# mirrored.net
KiCad netlist of a schematic drawn in EAGLE
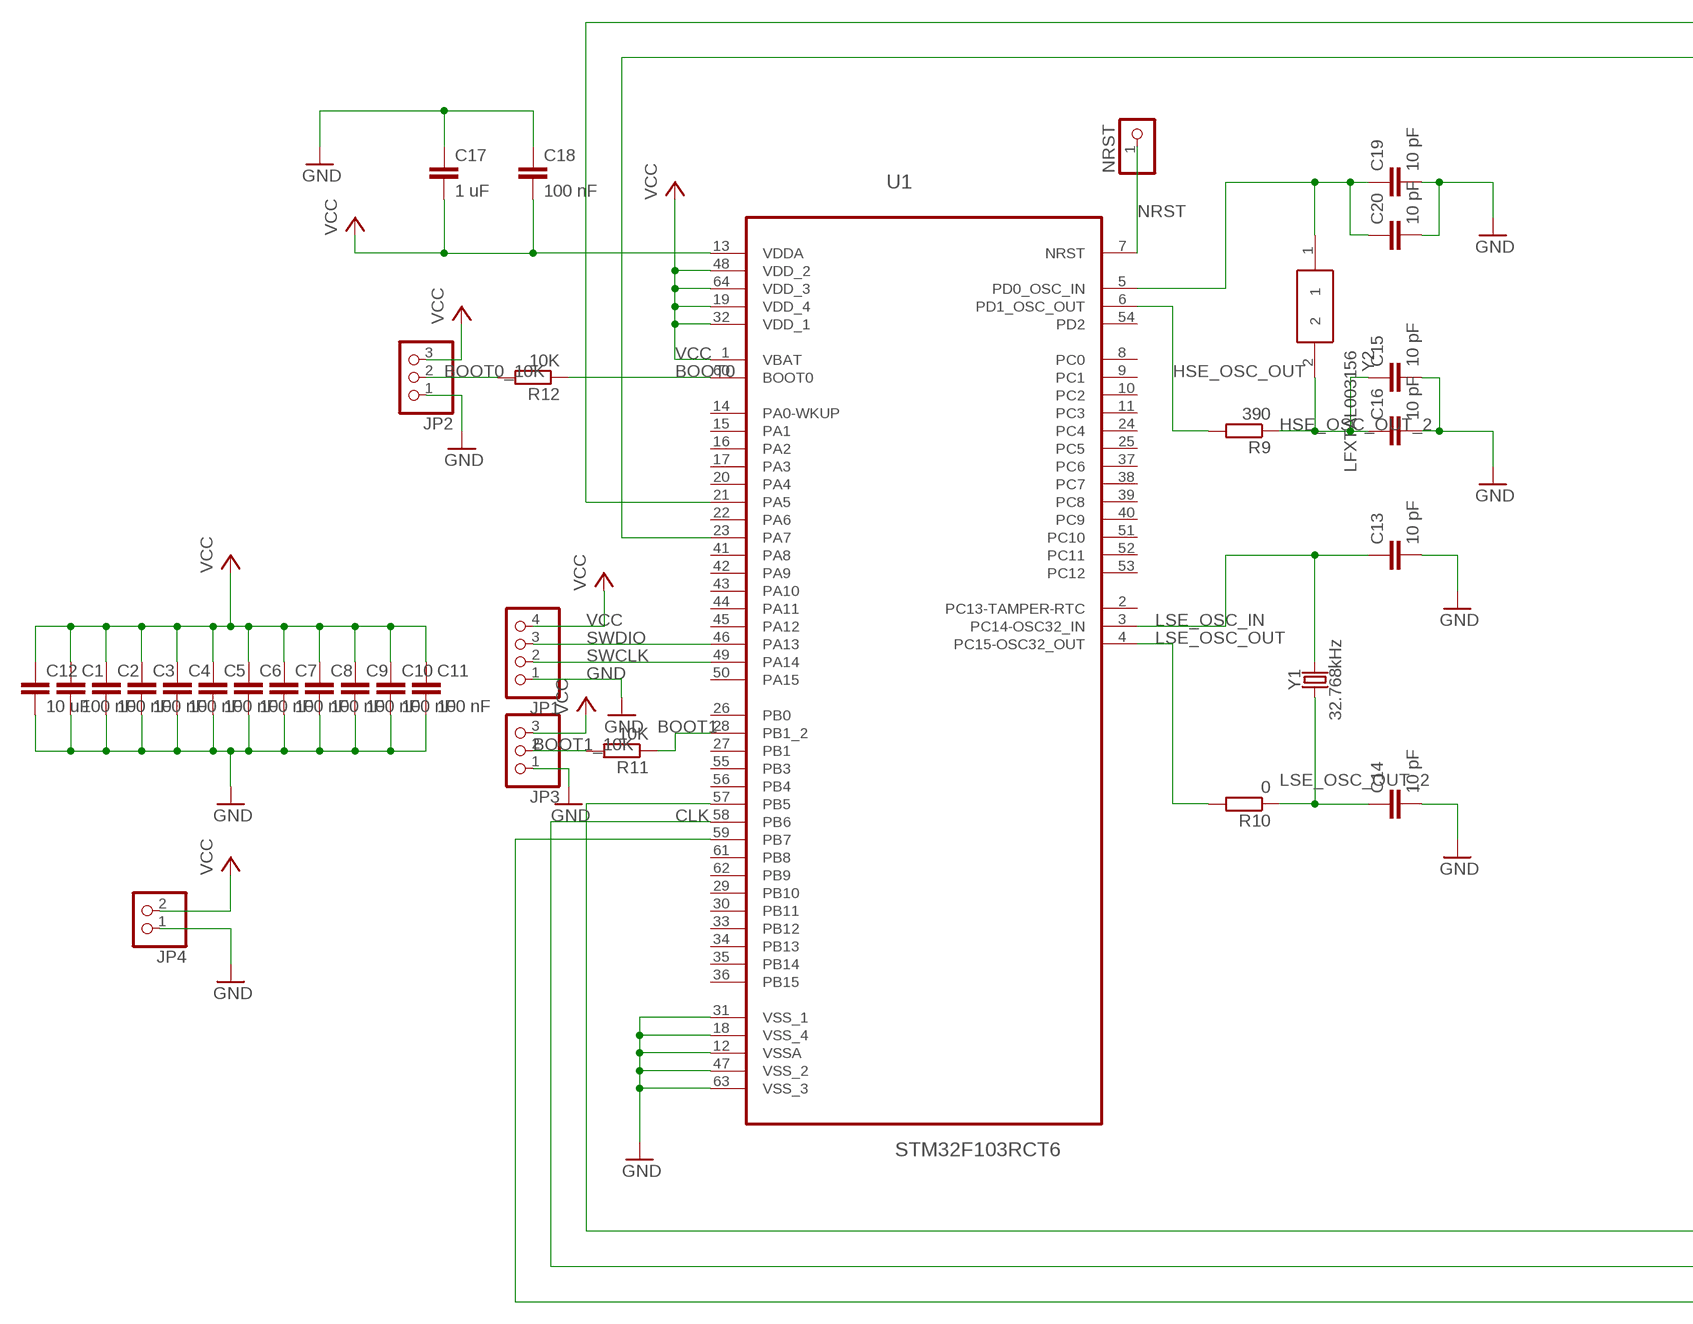
[diagram p0: schematic, sheet 1, part 1 of 2]
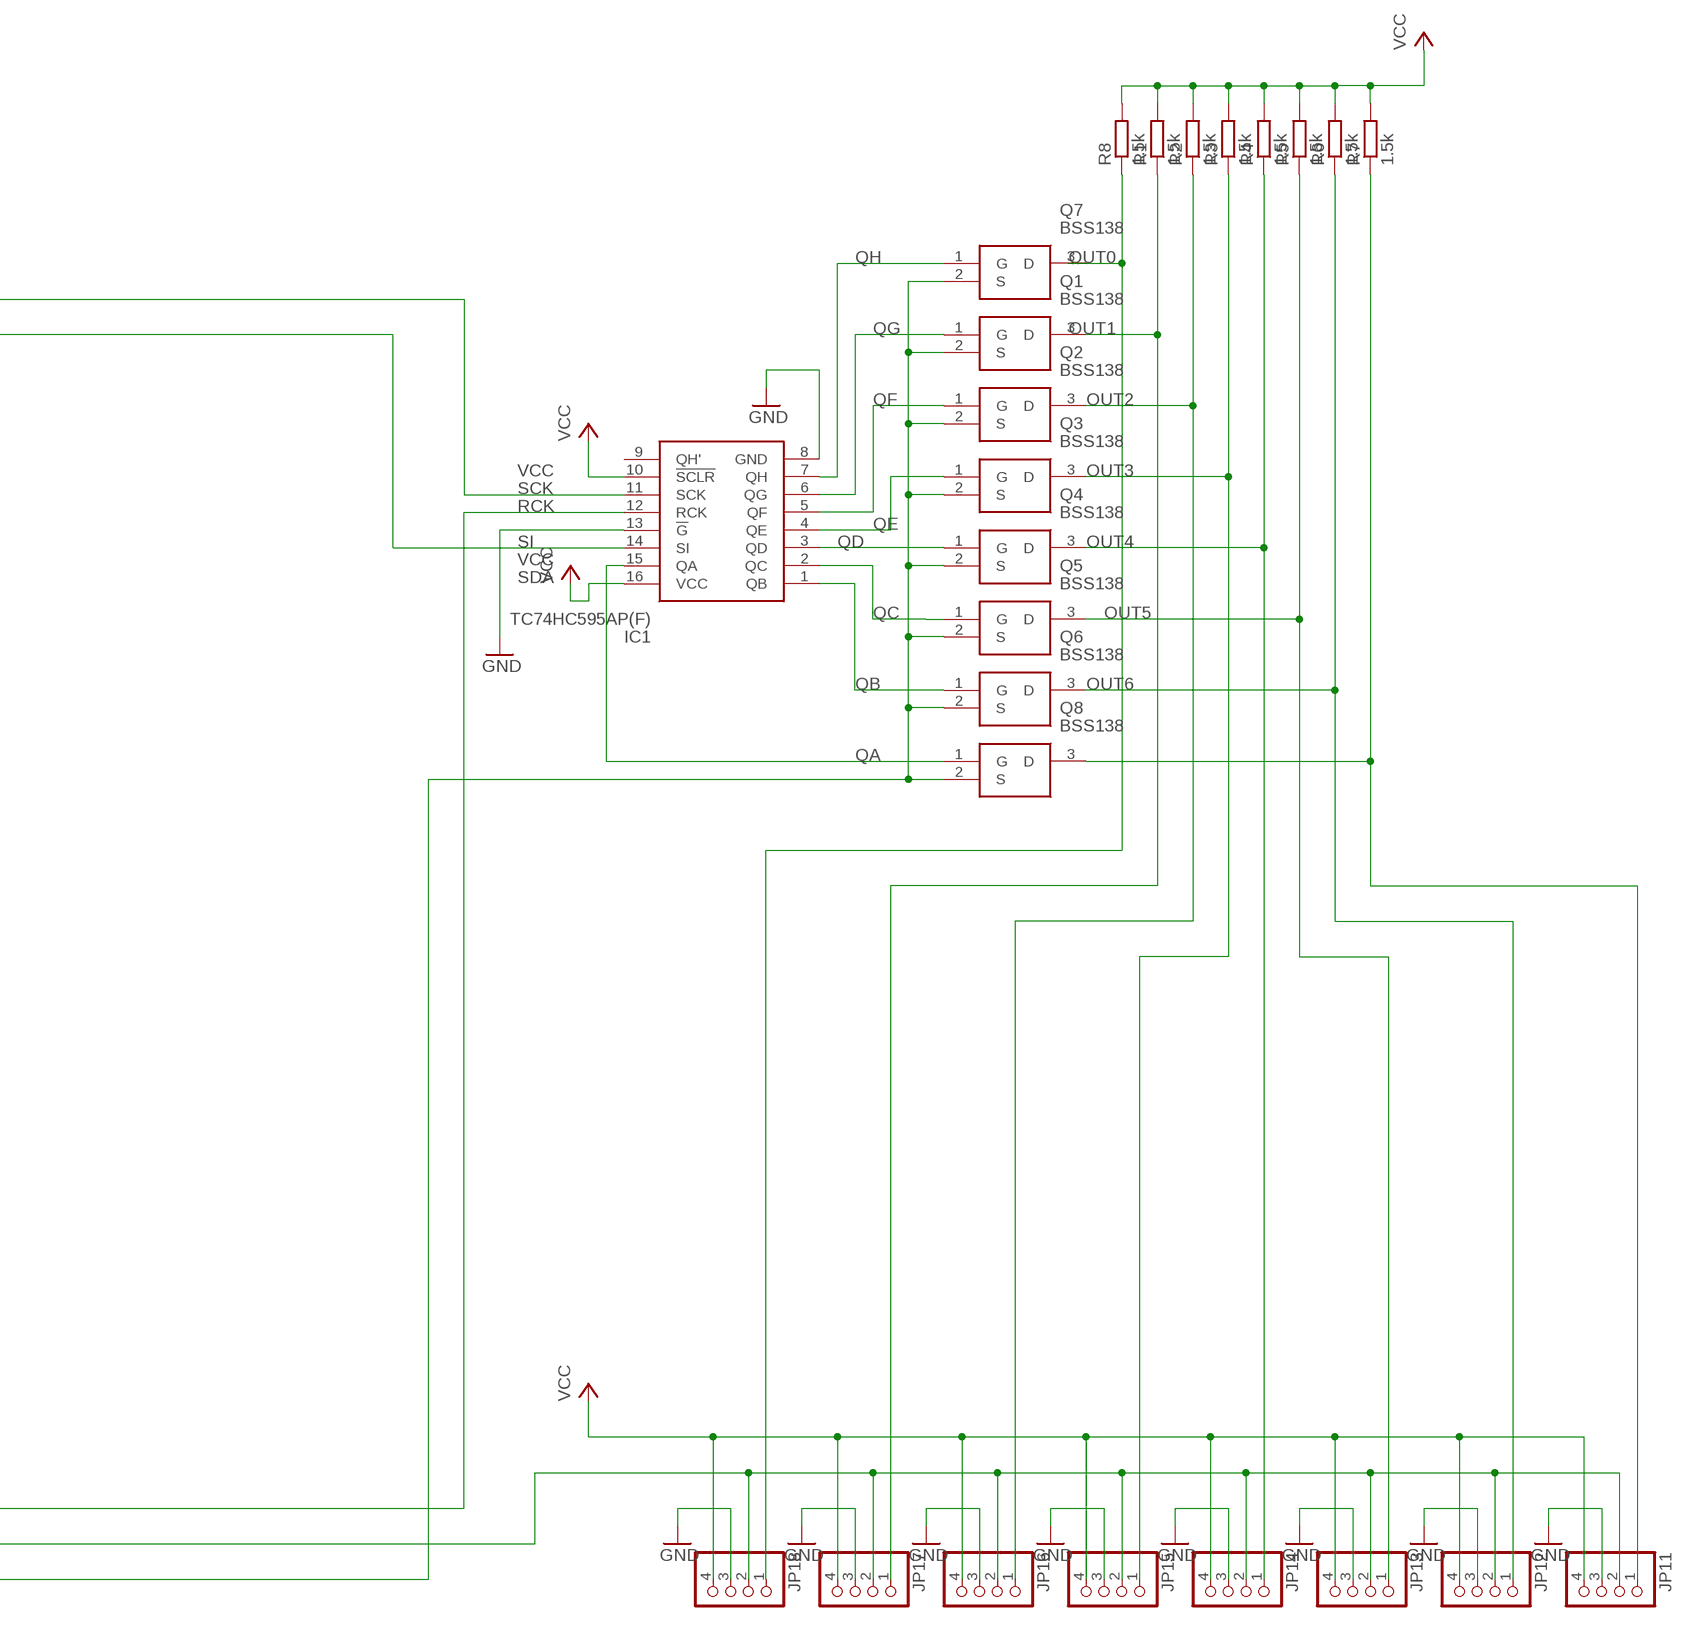
[diagram p1: schematic, sheet 1, part 2 of 2]

(export (version "E")
  (design (tool "Eeschema 10.0.6"))
  (components
    (comp (ref "C1")
      (value "100 nF")
      (footprint "eagle-import:C0603")
      (libsource (lib "eagle-import") (part "C-EUC0603"))
    )
    (comp (ref "C2")
      (value "100 nF")
      (footprint "eagle-import:C0603")
      (libsource (lib "eagle-import") (part "C-EUC0603"))
    )
    (comp (ref "C3")
      (value "100 nF")
      (footprint "eagle-import:C0603")
      (libsource (lib "eagle-import") (part "C-EUC0603"))
    )
    (comp (ref "C4")
      (value "100 nF")
      (footprint "eagle-import:C0603")
      (libsource (lib "eagle-import") (part "C-EUC0603"))
    )
    (comp (ref "C5")
      (value "100 nF")
      (footprint "eagle-import:C0603")
      (libsource (lib "eagle-import") (part "C-EUC0603"))
    )
    (comp (ref "C6")
      (value "100 nF")
      (footprint "eagle-import:C0603")
      (libsource (lib "eagle-import") (part "C-EUC0603"))
    )
    (comp (ref "C7")
      (value "100 nF")
      (footprint "eagle-import:C0603")
      (libsource (lib "eagle-import") (part "C-EUC0603"))
    )
    (comp (ref "C8")
      (value "100 nF")
      (footprint "eagle-import:C0603")
      (libsource (lib "eagle-import") (part "C-EUC0603"))
    )
    (comp (ref "C9")
      (value "100 nF")
      (footprint "eagle-import:C0603")
      (libsource (lib "eagle-import") (part "C-EUC0603"))
    )
    (comp (ref "C10")
      (value "100 nF")
      (footprint "eagle-import:C0603")
      (libsource (lib "eagle-import") (part "C-EUC0603"))
    )
    (comp (ref "C11")
      (value "100 nF")
      (footprint "eagle-import:C0603")
      (libsource (lib "eagle-import") (part "C-EUC0603"))
    )
    (comp (ref "C12")
      (value "10 uF")
      (footprint "eagle-import:C0603")
      (libsource (lib "eagle-import") (part "resistor_348_C-EUC0603"))
    )
    (comp (ref "C13")
      (value "10 pF")
      (footprint "eagle-import:C0805")
      (libsource (lib "eagle-import") (part "resistor_348_C-EUC0805"))
    )
    (comp (ref "C14")
      (value "10 pF")
      (footprint "eagle-import:C0805")
      (libsource (lib "eagle-import") (part "resistor_348_C-EUC0805"))
    )
    (comp (ref "C15")
      (value "10 pF")
      (footprint "eagle-import:C0805")
      (libsource (lib "eagle-import") (part "resistor_348_C-EUC0805"))
    )
    (comp (ref "C16")
      (value "10 pF")
      (footprint "eagle-import:C0805")
      (libsource (lib "eagle-import") (part "resistor_348_C-EUC0805"))
    )
    (comp (ref "C17")
      (value "1 uF")
      (footprint "eagle-import:C0603")
      (libsource (lib "eagle-import") (part "C-EUC0603"))
    )
    (comp (ref "C18")
      (value "100 nF")
      (footprint "eagle-import:C0603")
      (libsource (lib "eagle-import") (part "C-EUC0603"))
    )
    (comp (ref "C19")
      (value "10 pF")
      (footprint "eagle-import:C0805")
      (libsource (lib "eagle-import") (part "resistor_348_C-EUC0805"))
    )
    (comp (ref "C20")
      (value "10 pF")
      (footprint "eagle-import:C0805")
      (libsource (lib "eagle-import") (part "resistor_348_C-EUC0805"))
    )
    (comp (ref "IC1")
      (value "TC74HC595AP(F)")
      (footprint "eagle-import:DIP762W60P254L1925H445Q16N")
      (fields (field (name "RS_PART_NUMBER") "5400095P"))
      (libsource (lib "eagle-import") (part "TC74HC595AP(F)"))
    )
    (comp (ref "JP1")
      (value "PINHD-1X4")
      (footprint "eagle-import:1X04")
      (libsource (lib "eagle-import") (part "PINHD-1X4"))
    )
    (comp (ref "JP2")
      (value "PINHD-1X3")
      (footprint "eagle-import:1X03")
      (libsource (lib "eagle-import") (part "PINHD-1X3"))
    )
    (comp (ref "JP3")
      (value "PINHD-1X3")
      (footprint "eagle-import:1X03")
      (libsource (lib "eagle-import") (part "PINHD-1X3"))
    )
    (comp (ref "JP4")
      (value "PINHD-1X2")
      (footprint "eagle-import:1X02")
      (libsource (lib "eagle-import") (part "PINHD-1X2"))
    )
    (comp (ref "JP11")
      (value "PINHD-1X4")
      (footprint "eagle-import:1X04")
      (libsource (lib "eagle-import") (part "PINHD-1X4"))
    )
    (comp (ref "JP12")
      (value "PINHD-1X4")
      (footprint "eagle-import:1X04")
      (libsource (lib "eagle-import") (part "PINHD-1X4"))
    )
    (comp (ref "JP13")
      (value "PINHD-1X4")
      (footprint "eagle-import:1X04")
      (libsource (lib "eagle-import") (part "PINHD-1X4"))
    )
    (comp (ref "JP14")
      (value "PINHD-1X4")
      (footprint "eagle-import:1X04")
      (libsource (lib "eagle-import") (part "PINHD-1X4"))
    )
    (comp (ref "JP15")
      (value "PINHD-1X4")
      (footprint "eagle-import:1X04")
      (libsource (lib "eagle-import") (part "PINHD-1X4"))
    )
    (comp (ref "JP16")
      (value "PINHD-1X4")
      (footprint "eagle-import:1X04")
      (libsource (lib "eagle-import") (part "PINHD-1X4"))
    )
    (comp (ref "JP17")
      (value "PINHD-1X4")
      (footprint "eagle-import:1X04")
      (libsource (lib "eagle-import") (part "PINHD-1X4"))
    )
    (comp (ref "JP18")
      (value "PINHD-1X4")
      (footprint "eagle-import:1X04")
      (libsource (lib "eagle-import") (part "PINHD-1X4"))
    )
    (comp (ref "NRST")
      (value "PINHD-1X1")
      (footprint "eagle-import:1X01")
      (libsource (lib "eagle-import") (part "PINHD-1X1"))
    )
    (comp (ref "Q1")
      (value "BSS138")
      (footprint "eagle-import:SOT95P240X120-3N")
      (fields (field (name "MOUSER_PART_NUMBER") "512-BSS138") (field (name "RS_PART_NUMBER") "1241694"))
      (libsource (lib "eagle-import") (part "BSS138"))
    )
    (comp (ref "Q2")
      (value "BSS138")
      (footprint "eagle-import:SOT95P240X120-3N")
      (fields (field (name "MOUSER_PART_NUMBER") "512-BSS138") (field (name "RS_PART_NUMBER") "1241694"))
      (libsource (lib "eagle-import") (part "BSS138"))
    )
    (comp (ref "Q3")
      (value "BSS138")
      (footprint "eagle-import:SOT95P240X120-3N")
      (fields (field (name "MOUSER_PART_NUMBER") "512-BSS138") (field (name "RS_PART_NUMBER") "1241694"))
      (libsource (lib "eagle-import") (part "BSS138"))
    )
    (comp (ref "Q4")
      (value "BSS138")
      (footprint "eagle-import:SOT95P240X120-3N")
      (fields (field (name "MOUSER_PART_NUMBER") "512-BSS138") (field (name "RS_PART_NUMBER") "1241694"))
      (libsource (lib "eagle-import") (part "BSS138"))
    )
    (comp (ref "Q5")
      (value "BSS138")
      (footprint "eagle-import:SOT95P240X120-3N")
      (fields (field (name "MOUSER_PART_NUMBER") "512-BSS138") (field (name "RS_PART_NUMBER") "1241694"))
      (libsource (lib "eagle-import") (part "BSS138"))
    )
    (comp (ref "Q6")
      (value "BSS138")
      (footprint "eagle-import:SOT95P240X120-3N")
      (fields (field (name "MOUSER_PART_NUMBER") "512-BSS138") (field (name "RS_PART_NUMBER") "1241694"))
      (libsource (lib "eagle-import") (part "BSS138"))
    )
    (comp (ref "Q7")
      (value "BSS138")
      (footprint "eagle-import:SOT95P240X120-3N")
      (fields (field (name "MOUSER_PART_NUMBER") "512-BSS138") (field (name "RS_PART_NUMBER") "1241694"))
      (libsource (lib "eagle-import") (part "BSS138"))
    )
    (comp (ref "Q8")
      (value "BSS138")
      (footprint "eagle-import:SOT95P240X120-3N")
      (fields (field (name "MOUSER_PART_NUMBER") "512-BSS138") (field (name "RS_PART_NUMBER") "1241694"))
      (libsource (lib "eagle-import") (part "BSS138"))
    )
    (comp (ref "R1")
      (value "1.5k")
      (footprint "eagle-import:0207_15")
      (libsource (lib "eagle-import") (part "R-EU_0207/15"))
    )
    (comp (ref "R2")
      (value "1.5k")
      (footprint "eagle-import:0207_15")
      (libsource (lib "eagle-import") (part "R-EU_0207/15"))
    )
    (comp (ref "R3")
      (value "1.5k")
      (footprint "eagle-import:0207_15")
      (libsource (lib "eagle-import") (part "R-EU_0207/15"))
    )
    (comp (ref "R4")
      (value "1.5k")
      (footprint "eagle-import:0207_15")
      (libsource (lib "eagle-import") (part "R-EU_0207/15"))
    )
    (comp (ref "R5")
      (value "1.5k")
      (footprint "eagle-import:0207_15")
      (libsource (lib "eagle-import") (part "R-EU_0207/15"))
    )
    (comp (ref "R6")
      (value "1.5k")
      (footprint "eagle-import:0207_15")
      (libsource (lib "eagle-import") (part "R-EU_0207/15"))
    )
    (comp (ref "R7")
      (value "1.5k")
      (footprint "eagle-import:0207_15")
      (libsource (lib "eagle-import") (part "R-EU_0207/15"))
    )
    (comp (ref "R8")
      (value "1.5k")
      (footprint "eagle-import:0207_15")
      (libsource (lib "eagle-import") (part "R-EU_0207/15"))
    )
    (comp (ref "R9")
      (value "390")
      (footprint "eagle-import:0207_15")
      (libsource (lib "eagle-import") (part "R-EU_0207/15"))
    )
    (comp (ref "R10")
      (value "0")
      (footprint "eagle-import:0207_15")
      (libsource (lib "eagle-import") (part "R-EU_0207/15"))
    )
    (comp (ref "R11")
      (value "10K")
      (footprint "eagle-import:0207_15")
      (libsource (lib "eagle-import") (part "R-EU_0207/15"))
    )
    (comp (ref "R12")
      (value "10K")
      (footprint "eagle-import:0207_15")
      (libsource (lib "eagle-import") (part "R-EU_0207/15"))
    )
    (comp (ref "U1")
      (value "STM32F103RCT6")
      (footprint "eagle-import:QFP50P1200X1200X160-64N")
      (fields (field (name "MF") "STMicroelectronics"))
      (libsource (lib "eagle-import") (part "STM32F103RCT6"))
    )
    (comp (ref "Y1")
      (value "32.768kHz")
      (footprint "eagle-import:CRYSTAL-PTH-2X6-CYL")
      (libsource (lib "eagle-import") (part "CRYSTAL-32.768KHZPTH-2X6"))
    )
    (comp (ref "Y2")
      (value "LFXTAL003156")
      (footprint "eagle-import:IQD-HC-49-4H")
      (fields (field (name "RS_PART_NUMBER") "1533666"))
      (libsource (lib "eagle-import") (part "LFXTAL003156"))
    )
  )
  (nets
    (net (code "1") (name "/BOOT0") (class "Default")
      (node (ref "R12") (pin "1") (pinfunction "1_1") (pintype "passive"))
      (node (ref "U1") (pin "60") (pinfunction "BOOT0_60") (pintype "passive"))
    )
    (net (code "2") (name "/BOOT0_10K") (class "Default")
      (node (ref "JP2") (pin "2") (pinfunction "2_2") (pintype "passive"))
      (node (ref "R12") (pin "2") (pinfunction "2_2") (pintype "passive"))
    )
    (net (code "3") (name "/BOOT1") (class "Default")
      (node (ref "R11") (pin "1") (pinfunction "1_1") (pintype "passive"))
      (node (ref "U1") (pin "28") (pinfunction "PB1_2_28") (pintype "bidirectional"))
    )
    (net (code "4") (name "/BOOT1_10K") (class "Default")
      (node (ref "JP3") (pin "2") (pinfunction "2_2") (pintype "passive"))
      (node (ref "R11") (pin "2") (pinfunction "2_2") (pintype "passive"))
    )
    (net (code "5") (name "/CLK") (class "Default")
      (node (ref "JP11") (pin "2") (pinfunction "2_2") (pintype "passive"))
      (node (ref "JP12") (pin "2") (pinfunction "2_2") (pintype "passive"))
      (node (ref "JP13") (pin "2") (pinfunction "2_2") (pintype "passive"))
      (node (ref "JP14") (pin "2") (pinfunction "2_2") (pintype "passive"))
      (node (ref "JP15") (pin "2") (pinfunction "2_2") (pintype "passive"))
      (node (ref "JP16") (pin "2") (pinfunction "2_2") (pintype "passive"))
      (node (ref "JP17") (pin "2") (pinfunction "2_2") (pintype "passive"))
      (node (ref "JP18") (pin "2") (pinfunction "2_2") (pintype "passive"))
      (node (ref "U1") (pin "58") (pinfunction "PB6_58") (pintype "bidirectional"))
    )
    (net (code "6") (name "/HSE_OSC_OUT") (class "Default")
      (node (ref "R9") (pin "2") (pinfunction "2_2") (pintype "passive"))
      (node (ref "U1") (pin "6") (pinfunction "PD1_OSC_OUT_6") (pintype "output"))
    )
    (net (code "7") (name "/HSE_OSC_OUT_2") (class "Default")
      (node (ref "C15") (pin "1") (pinfunction "1_1") (pintype "passive"))
      (node (ref "C16") (pin "1") (pinfunction "1_1") (pintype "passive"))
      (node (ref "R9") (pin "1") (pinfunction "1_1") (pintype "passive"))
      (node (ref "Y2") (pin "2") (pinfunction "2_2") (pintype "bidirectional"))
    )
    (net (code "8") (name "/LSE_OSC_IN") (class "Default")
      (node (ref "C13") (pin "1") (pinfunction "1_1") (pintype "passive"))
      (node (ref "U1") (pin "3") (pinfunction "PC14-OSC32_IN_3") (pintype "input"))
      (node (ref "Y1") (pin "2") (pinfunction "2_2") (pintype "passive"))
    )
    (net (code "9") (name "/LSE_OSC_OUT") (class "Default")
      (node (ref "R10") (pin "2") (pinfunction "2_2") (pintype "passive"))
      (node (ref "U1") (pin "4") (pinfunction "PC15-OSC32_OUT_4") (pintype "output"))
    )
    (net (code "10") (name "/LSE_OSC_OUT_2") (class "Default")
      (node (ref "C14") (pin "1") (pinfunction "1_1") (pintype "passive"))
      (node (ref "R10") (pin "1") (pinfunction "1_1") (pintype "passive"))
      (node (ref "Y1") (pin "1") (pinfunction "1_1") (pintype "passive"))
    )
    (net (code "11") (name "/NRST") (class "Default")
      (node (ref "NRST") (pin "1") (pinfunction "1_1") (pintype "passive"))
      (node (ref "U1") (pin "7") (pinfunction "NRST_7") (pintype "output"))
    )
    (net (code "12") (name "/OUT0") (class "Default")
      (node (ref "JP18") (pin "1") (pinfunction "1_1") (pintype "passive"))
      (node (ref "Q7") (pin "3") (pinfunction "D_3") (pintype "bidirectional"))
      (node (ref "R8") (pin "1") (pinfunction "1_1") (pintype "passive"))
    )
    (net (code "13") (name "/OUT1") (class "Default")
      (node (ref "JP17") (pin "1") (pinfunction "1_1") (pintype "passive"))
      (node (ref "Q1") (pin "3") (pinfunction "D_3") (pintype "bidirectional"))
      (node (ref "R1") (pin "1") (pinfunction "1_1") (pintype "passive"))
    )
    (net (code "14") (name "/OUT2") (class "Default")
      (node (ref "JP16") (pin "1") (pinfunction "1_1") (pintype "passive"))
      (node (ref "Q2") (pin "3") (pinfunction "D_3") (pintype "bidirectional"))
      (node (ref "R2") (pin "1") (pinfunction "1_1") (pintype "passive"))
    )
    (net (code "15") (name "/OUT3") (class "Default")
      (node (ref "JP15") (pin "1") (pinfunction "1_1") (pintype "passive"))
      (node (ref "Q3") (pin "3") (pinfunction "D_3") (pintype "bidirectional"))
      (node (ref "R3") (pin "1") (pinfunction "1_1") (pintype "passive"))
    )
    (net (code "16") (name "/OUT4") (class "Default")
      (node (ref "JP14") (pin "1") (pinfunction "1_1") (pintype "passive"))
      (node (ref "Q4") (pin "3") (pinfunction "D_3") (pintype "bidirectional"))
      (node (ref "R4") (pin "1") (pinfunction "1_1") (pintype "passive"))
    )
    (net (code "17") (name "/OUT5") (class "Default")
      (node (ref "JP13") (pin "1") (pinfunction "1_1") (pintype "passive"))
      (node (ref "Q5") (pin "3") (pinfunction "D_3") (pintype "bidirectional"))
      (node (ref "R5") (pin "1") (pinfunction "1_1") (pintype "passive"))
    )
    (net (code "18") (name "/OUT6") (class "Default")
      (node (ref "JP12") (pin "1") (pinfunction "1_1") (pintype "passive"))
      (node (ref "Q6") (pin "3") (pinfunction "D_3") (pintype "bidirectional"))
      (node (ref "R6") (pin "1") (pinfunction "1_1") (pintype "passive"))
    )
    (net (code "19") (name "/QA") (class "Default")
      (node (ref "IC1") (pin "15") (pinfunction "QA_15") (pintype "bidirectional"))
      (node (ref "Q8") (pin "1") (pinfunction "G_1") (pintype "bidirectional"))
    )
    (net (code "20") (name "/QB") (class "Default")
      (node (ref "IC1") (pin "1") (pinfunction "QB_1") (pintype "bidirectional"))
      (node (ref "Q6") (pin "1") (pinfunction "G_1") (pintype "bidirectional"))
    )
    (net (code "21") (name "/QC") (class "Default")
      (node (ref "IC1") (pin "2") (pinfunction "QC_2") (pintype "bidirectional"))
      (node (ref "Q5") (pin "1") (pinfunction "G_1") (pintype "bidirectional"))
    )
    (net (code "22") (name "/QD") (class "Default")
      (node (ref "IC1") (pin "3") (pinfunction "QD_3") (pintype "bidirectional"))
      (node (ref "Q4") (pin "1") (pinfunction "G_1") (pintype "bidirectional"))
    )
    (net (code "23") (name "/QE") (class "Default")
      (node (ref "IC1") (pin "4") (pinfunction "QE_4") (pintype "bidirectional"))
      (node (ref "Q3") (pin "1") (pinfunction "G_1") (pintype "bidirectional"))
    )
    (net (code "24") (name "/QF") (class "Default")
      (node (ref "IC1") (pin "5") (pinfunction "QF_5") (pintype "bidirectional"))
      (node (ref "Q2") (pin "1") (pinfunction "G_1") (pintype "bidirectional"))
    )
    (net (code "25") (name "/QG") (class "Default")
      (node (ref "IC1") (pin "6") (pinfunction "QG_6") (pintype "bidirectional"))
      (node (ref "Q1") (pin "1") (pinfunction "G_1") (pintype "bidirectional"))
    )
    (net (code "26") (name "/QH") (class "Default")
      (node (ref "IC1") (pin "7") (pinfunction "QH_7") (pintype "bidirectional"))
      (node (ref "Q7") (pin "1") (pinfunction "G_1") (pintype "bidirectional"))
    )
    (net (code "27") (name "/RCK") (class "Default")
      (node (ref "IC1") (pin "12") (pinfunction "RCK_12") (pintype "bidirectional"))
      (node (ref "U1") (pin "57") (pinfunction "PB5_57") (pintype "bidirectional"))
    )
    (net (code "28") (name "/SCK") (class "Default")
      (node (ref "IC1") (pin "11") (pinfunction "SCK_11") (pintype "bidirectional"))
      (node (ref "U1") (pin "21") (pinfunction "PA5_21") (pintype "bidirectional"))
    )
    (net (code "29") (name "/SDA") (class "Default")
      (node (ref "Q1") (pin "2") (pinfunction "S_2") (pintype "bidirectional"))
      (node (ref "Q2") (pin "2") (pinfunction "S_2") (pintype "bidirectional"))
      (node (ref "Q3") (pin "2") (pinfunction "S_2") (pintype "bidirectional"))
      (node (ref "Q4") (pin "2") (pinfunction "S_2") (pintype "bidirectional"))
      (node (ref "Q5") (pin "2") (pinfunction "S_2") (pintype "bidirectional"))
      (node (ref "Q6") (pin "2") (pinfunction "S_2") (pintype "bidirectional"))
      (node (ref "Q7") (pin "2") (pinfunction "S_2") (pintype "bidirectional"))
      (node (ref "Q8") (pin "2") (pinfunction "S_2") (pintype "bidirectional"))
      (node (ref "U1") (pin "59") (pinfunction "PB7_59") (pintype "power_in"))
    )
    (net (code "30") (name "/SI") (class "Default")
      (node (ref "IC1") (pin "14") (pinfunction "SI_14") (pintype "bidirectional"))
      (node (ref "U1") (pin "23") (pinfunction "PA7_23") (pintype "power_in"))
    )
    (net (code "31") (name "/SWCLK") (class "Default")
      (node (ref "JP1") (pin "2") (pinfunction "2_2") (pintype "passive"))
      (node (ref "U1") (pin "49") (pinfunction "PA14_49") (pintype "bidirectional"))
    )
    (net (code "32") (name "/SWDIO") (class "Default")
      (node (ref "JP1") (pin "3") (pinfunction "3_3") (pintype "passive"))
      (node (ref "U1") (pin "46") (pinfunction "PA13_46") (pintype "bidirectional"))
    )
    (net (code "33") (name "GND") (class "Default")
      (node (ref "C1") (pin "2") (pinfunction "2_2") (pintype "passive"))
      (node (ref "C10") (pin "2") (pinfunction "2_2") (pintype "passive"))
      (node (ref "C11") (pin "2") (pinfunction "2_2") (pintype "passive"))
      (node (ref "C12") (pin "2") (pinfunction "2_2") (pintype "passive"))
      (node (ref "C13") (pin "2") (pinfunction "2_2") (pintype "passive"))
      (node (ref "C14") (pin "2") (pinfunction "2_2") (pintype "passive"))
      (node (ref "C15") (pin "2") (pinfunction "2_2") (pintype "passive"))
      (node (ref "C16") (pin "2") (pinfunction "2_2") (pintype "passive"))
      (node (ref "C17") (pin "1") (pinfunction "1_1") (pintype "passive"))
      (node (ref "C18") (pin "1") (pinfunction "1_1") (pintype "passive"))
      (node (ref "C19") (pin "2") (pinfunction "2_2") (pintype "passive"))
      (node (ref "C2") (pin "2") (pinfunction "2_2") (pintype "passive"))
      (node (ref "C20") (pin "2") (pinfunction "2_2") (pintype "passive"))
      (node (ref "C3") (pin "2") (pinfunction "2_2") (pintype "passive"))
      (node (ref "C4") (pin "2") (pinfunction "2_2") (pintype "passive"))
      (node (ref "C5") (pin "2") (pinfunction "2_2") (pintype "passive"))
      (node (ref "C6") (pin "2") (pinfunction "2_2") (pintype "passive"))
      (node (ref "C7") (pin "2") (pinfunction "2_2") (pintype "passive"))
      (node (ref "C8") (pin "2") (pinfunction "2_2") (pintype "passive"))
      (node (ref "C9") (pin "2") (pinfunction "2_2") (pintype "passive"))
      (node (ref "IC1") (pin "13") (pinfunction "~{G}_13") (pintype "bidirectional"))
      (node (ref "IC1") (pin "8") (pinfunction "GND_8") (pintype "bidirectional"))
      (node (ref "JP1") (pin "1") (pinfunction "1_1") (pintype "passive"))
      (node (ref "JP11") (pin "3") (pinfunction "3_3") (pintype "passive"))
      (node (ref "JP12") (pin "3") (pinfunction "3_3") (pintype "passive"))
      (node (ref "JP13") (pin "3") (pinfunction "3_3") (pintype "passive"))
      (node (ref "JP14") (pin "3") (pinfunction "3_3") (pintype "passive"))
      (node (ref "JP15") (pin "3") (pinfunction "3_3") (pintype "passive"))
      (node (ref "JP16") (pin "3") (pinfunction "3_3") (pintype "passive"))
      (node (ref "JP17") (pin "3") (pinfunction "3_3") (pintype "passive"))
      (node (ref "JP18") (pin "3") (pinfunction "3_3") (pintype "passive"))
      (node (ref "JP2") (pin "1") (pinfunction "1_1") (pintype "passive"))
      (node (ref "JP3") (pin "1") (pinfunction "1_1") (pintype "passive"))
      (node (ref "JP4") (pin "1") (pinfunction "1_1") (pintype "passive"))
      (node (ref "U1") (pin "12") (pinfunction "VSSA_12") (pintype "passive"))
      (node (ref "U1") (pin "18") (pinfunction "VSS_4_18") (pintype "passive"))
      (node (ref "U1") (pin "31") (pinfunction "VSS_1_31") (pintype "passive"))
      (node (ref "U1") (pin "47") (pinfunction "VSS_2_47") (pintype "passive"))
      (node (ref "U1") (pin "63") (pinfunction "VSS_3_63") (pintype "passive"))
    )
    (net (code "34") (name "Net-(Q8-D)") (class "Default")
      (node (ref "JP11") (pin "1") (pinfunction "1_1") (pintype "passive"))
      (node (ref "Q8") (pin "3") (pinfunction "D_3") (pintype "bidirectional"))
      (node (ref "R7") (pin "1") (pinfunction "1_1") (pintype "passive"))
    )
    (net (code "35") (name "Net-(U1-PD0_OSC_IN)") (class "Default")
      (node (ref "C19") (pin "1") (pinfunction "1_1") (pintype "passive"))
      (node (ref "C20") (pin "1") (pinfunction "1_1") (pintype "passive"))
      (node (ref "U1") (pin "5") (pinfunction "PD0_OSC_IN_5") (pintype "input"))
      (node (ref "Y2") (pin "1") (pinfunction "1_1") (pintype "bidirectional"))
    )
    (net (code "36") (name "VCC") (class "Default")
      (node (ref "C1") (pin "1") (pinfunction "1_1") (pintype "passive"))
      (node (ref "C10") (pin "1") (pinfunction "1_1") (pintype "passive"))
      (node (ref "C11") (pin "1") (pinfunction "1_1") (pintype "passive"))
      (node (ref "C12") (pin "1") (pinfunction "1_1") (pintype "passive"))
      (node (ref "C17") (pin "2") (pinfunction "2_2") (pintype "passive"))
      (node (ref "C18") (pin "2") (pinfunction "2_2") (pintype "passive"))
      (node (ref "C2") (pin "1") (pinfunction "1_1") (pintype "passive"))
      (node (ref "C3") (pin "1") (pinfunction "1_1") (pintype "passive"))
      (node (ref "C4") (pin "1") (pinfunction "1_1") (pintype "passive"))
      (node (ref "C5") (pin "1") (pinfunction "1_1") (pintype "passive"))
      (node (ref "C6") (pin "1") (pinfunction "1_1") (pintype "passive"))
      (node (ref "C7") (pin "1") (pinfunction "1_1") (pintype "passive"))
      (node (ref "C8") (pin "1") (pinfunction "1_1") (pintype "passive"))
      (node (ref "C9") (pin "1") (pinfunction "1_1") (pintype "passive"))
      (node (ref "IC1") (pin "10") (pinfunction "~{SCLR}_10") (pintype "bidirectional"))
      (node (ref "IC1") (pin "16") (pinfunction "VCC_16") (pintype "bidirectional"))
      (node (ref "JP1") (pin "4") (pinfunction "4_4") (pintype "passive"))
      (node (ref "JP11") (pin "4") (pinfunction "4_4") (pintype "passive"))
      (node (ref "JP12") (pin "4") (pinfunction "4_4") (pintype "passive"))
      (node (ref "JP13") (pin "4") (pinfunction "4_4") (pintype "passive"))
      (node (ref "JP14") (pin "4") (pinfunction "4_4") (pintype "passive"))
      (node (ref "JP15") (pin "4") (pinfunction "4_4") (pintype "passive"))
      (node (ref "JP16") (pin "4") (pinfunction "4_4") (pintype "passive"))
      (node (ref "JP17") (pin "4") (pinfunction "4_4") (pintype "passive"))
      (node (ref "JP18") (pin "4") (pinfunction "4_4") (pintype "passive"))
      (node (ref "JP2") (pin "3") (pinfunction "3_3") (pintype "passive"))
      (node (ref "JP3") (pin "3") (pinfunction "3_3") (pintype "passive"))
      (node (ref "JP4") (pin "2") (pinfunction "2_2") (pintype "passive"))
      (node (ref "R1") (pin "2") (pinfunction "2_2") (pintype "passive"))
      (node (ref "R2") (pin "2") (pinfunction "2_2") (pintype "passive"))
      (node (ref "R3") (pin "2") (pinfunction "2_2") (pintype "passive"))
      (node (ref "R4") (pin "2") (pinfunction "2_2") (pintype "passive"))
      (node (ref "R5") (pin "2") (pinfunction "2_2") (pintype "passive"))
      (node (ref "R6") (pin "2") (pinfunction "2_2") (pintype "passive"))
      (node (ref "R7") (pin "2") (pinfunction "2_2") (pintype "passive"))
      (node (ref "R8") (pin "2") (pinfunction "2_2") (pintype "passive"))
      (node (ref "U1") (pin "1") (pinfunction "VBAT_1") (pintype "input"))
      (node (ref "U1") (pin "13") (pinfunction "VDDA_13") (pintype "power_in"))
      (node (ref "U1") (pin "19") (pinfunction "VDD_4_19") (pintype "power_in"))
      (node (ref "U1") (pin "32") (pinfunction "VDD_1_32") (pintype "power_in"))
      (node (ref "U1") (pin "48") (pinfunction "VDD_2_48") (pintype "power_in"))
      (node (ref "U1") (pin "64") (pinfunction "VDD_3_64") (pintype "power_in"))
    )
    (net (code "37") (name "unconnected-(IC1-QH'-Pad9)") (class "Default")
      (node (ref "IC1") (pin "9") (pinfunction "QH'_9") (pintype "bidirectional"))
    )
    (net (code "38") (name "unconnected-(U1-PA0-WKUP-Pad14)") (class "Default")
      (node (ref "U1") (pin "14") (pinfunction "PA0-WKUP_14") (pintype "bidirectional"))
    )
    (net (code "39") (name "unconnected-(U1-PA1-Pad15)") (class "Default")
      (node (ref "U1") (pin "15") (pinfunction "PA1_15") (pintype "bidirectional"))
    )
    (net (code "40") (name "unconnected-(U1-PA2-Pad16)") (class "Default")
      (node (ref "U1") (pin "16") (pinfunction "PA2_16") (pintype "bidirectional"))
    )
    (net (code "41") (name "unconnected-(U1-PA3-Pad17)") (class "Default")
      (node (ref "U1") (pin "17") (pinfunction "PA3_17") (pintype "bidirectional"))
    )
    (net (code "42") (name "unconnected-(U1-PA4-Pad20)") (class "Default")
      (node (ref "U1") (pin "20") (pinfunction "PA4_20") (pintype "bidirectional"))
    )
    (net (code "43") (name "unconnected-(U1-PA6-Pad22)") (class "Default")
      (node (ref "U1") (pin "22") (pinfunction "PA6_22") (pintype "bidirectional"))
    )
    (net (code "44") (name "unconnected-(U1-PA8-Pad41)") (class "Default")
      (node (ref "U1") (pin "41") (pinfunction "PA8_41") (pintype "bidirectional"))
    )
    (net (code "45") (name "unconnected-(U1-PA9-Pad42)") (class "Default")
      (node (ref "U1") (pin "42") (pinfunction "PA9_42") (pintype "bidirectional"))
    )
    (net (code "46") (name "unconnected-(U1-PA10-Pad43)") (class "Default")
      (node (ref "U1") (pin "43") (pinfunction "PA10_43") (pintype "bidirectional"))
    )
    (net (code "47") (name "unconnected-(U1-PA11-Pad44)") (class "Default")
      (node (ref "U1") (pin "44") (pinfunction "PA11_44") (pintype "bidirectional"))
    )
    (net (code "48") (name "unconnected-(U1-PA12-Pad45)") (class "Default")
      (node (ref "U1") (pin "45") (pinfunction "PA12_45") (pintype "bidirectional"))
    )
    (net (code "49") (name "unconnected-(U1-PA15-Pad50)") (class "Default")
      (node (ref "U1") (pin "50") (pinfunction "PA15_50") (pintype "bidirectional"))
    )
    (net (code "50") (name "unconnected-(U1-PB0-Pad26)") (class "Default")
      (node (ref "U1") (pin "26") (pinfunction "PB0_26") (pintype "bidirectional"))
    )
    (net (code "51") (name "unconnected-(U1-PB1-Pad27)") (class "Default")
      (node (ref "U1") (pin "27") (pinfunction "PB1_27") (pintype "bidirectional"))
    )
    (net (code "52") (name "unconnected-(U1-PB3-Pad55)") (class "Default")
      (node (ref "U1") (pin "55") (pinfunction "PB3_55") (pintype "bidirectional"))
    )
    (net (code "53") (name "unconnected-(U1-PB4-Pad56)") (class "Default")
      (node (ref "U1") (pin "56") (pinfunction "PB4_56") (pintype "bidirectional"))
    )
    (net (code "54") (name "unconnected-(U1-PB8-Pad61)") (class "Default")
      (node (ref "U1") (pin "61") (pinfunction "PB8_61") (pintype "bidirectional"))
    )
    (net (code "55") (name "unconnected-(U1-PB9-Pad62)") (class "Default")
      (node (ref "U1") (pin "62") (pinfunction "PB9_62") (pintype "bidirectional"))
    )
    (net (code "56") (name "unconnected-(U1-PB10-Pad29)") (class "Default")
      (node (ref "U1") (pin "29") (pinfunction "PB10_29") (pintype "bidirectional"))
    )
    (net (code "57") (name "unconnected-(U1-PB11-Pad30)") (class "Default")
      (node (ref "U1") (pin "30") (pinfunction "PB11_30") (pintype "bidirectional"))
    )
    (net (code "58") (name "unconnected-(U1-PB12-Pad33)") (class "Default")
      (node (ref "U1") (pin "33") (pinfunction "PB12_33") (pintype "bidirectional"))
    )
    (net (code "59") (name "unconnected-(U1-PB13-Pad34)") (class "Default")
      (node (ref "U1") (pin "34") (pinfunction "PB13_34") (pintype "bidirectional"))
    )
    (net (code "60") (name "unconnected-(U1-PB14-Pad35)") (class "Default")
      (node (ref "U1") (pin "35") (pinfunction "PB14_35") (pintype "bidirectional"))
    )
    (net (code "61") (name "unconnected-(U1-PB15-Pad36)") (class "Default")
      (node (ref "U1") (pin "36") (pinfunction "PB15_36") (pintype "bidirectional"))
    )
    (net (code "62") (name "unconnected-(U1-PC0-Pad8)") (class "Default")
      (node (ref "U1") (pin "8") (pinfunction "PC0_8") (pintype "bidirectional"))
    )
    (net (code "63") (name "unconnected-(U1-PC1-Pad9)") (class "Default")
      (node (ref "U1") (pin "9") (pinfunction "PC1_9") (pintype "bidirectional"))
    )
    (net (code "64") (name "unconnected-(U1-PC2-Pad10)") (class "Default")
      (node (ref "U1") (pin "10") (pinfunction "PC2_10") (pintype "bidirectional"))
    )
    (net (code "65") (name "unconnected-(U1-PC3-Pad11)") (class "Default")
      (node (ref "U1") (pin "11") (pinfunction "PC3_11") (pintype "bidirectional"))
    )
    (net (code "66") (name "unconnected-(U1-PC4-Pad24)") (class "Default")
      (node (ref "U1") (pin "24") (pinfunction "PC4_24") (pintype "passive"))
    )
    (net (code "67") (name "unconnected-(U1-PC5-Pad25)") (class "Default")
      (node (ref "U1") (pin "25") (pinfunction "PC5_25") (pintype "bidirectional"))
    )
    (net (code "68") (name "unconnected-(U1-PC6-Pad37)") (class "Default")
      (node (ref "U1") (pin "37") (pinfunction "PC6_37") (pintype "bidirectional"))
    )
    (net (code "69") (name "unconnected-(U1-PC7-Pad38)") (class "Default")
      (node (ref "U1") (pin "38") (pinfunction "PC7_38") (pintype "bidirectional"))
    )
    (net (code "70") (name "unconnected-(U1-PC8-Pad39)") (class "Default")
      (node (ref "U1") (pin "39") (pinfunction "PC8_39") (pintype "bidirectional"))
    )
    (net (code "71") (name "unconnected-(U1-PC9-Pad40)") (class "Default")
      (node (ref "U1") (pin "40") (pinfunction "PC9_40") (pintype "bidirectional"))
    )
    (net (code "72") (name "unconnected-(U1-PC10-Pad51)") (class "Default")
      (node (ref "U1") (pin "51") (pinfunction "PC10_51") (pintype "bidirectional"))
    )
    (net (code "73") (name "unconnected-(U1-PC11-Pad52)") (class "Default")
      (node (ref "U1") (pin "52") (pinfunction "PC11_52") (pintype "bidirectional"))
    )
    (net (code "74") (name "unconnected-(U1-PC12-Pad53)") (class "Default")
      (node (ref "U1") (pin "53") (pinfunction "PC12_53") (pintype "bidirectional"))
    )
    (net (code "75") (name "unconnected-(U1-PC13-TAMPER-RTC-Pad2)") (class "Default")
      (node (ref "U1") (pin "2") (pinfunction "PC13-TAMPER-RTC_2") (pintype "input"))
    )
    (net (code "76") (name "unconnected-(U1-PD2-Pad54)") (class "Default")
      (node (ref "U1") (pin "54") (pinfunction "PD2_54") (pintype "bidirectional"))
    )
  )
)
